# SCH_USB-Iker-Delicado_2025-02-14.net
KiCad netlist of a schematic drawn in EasyEDA
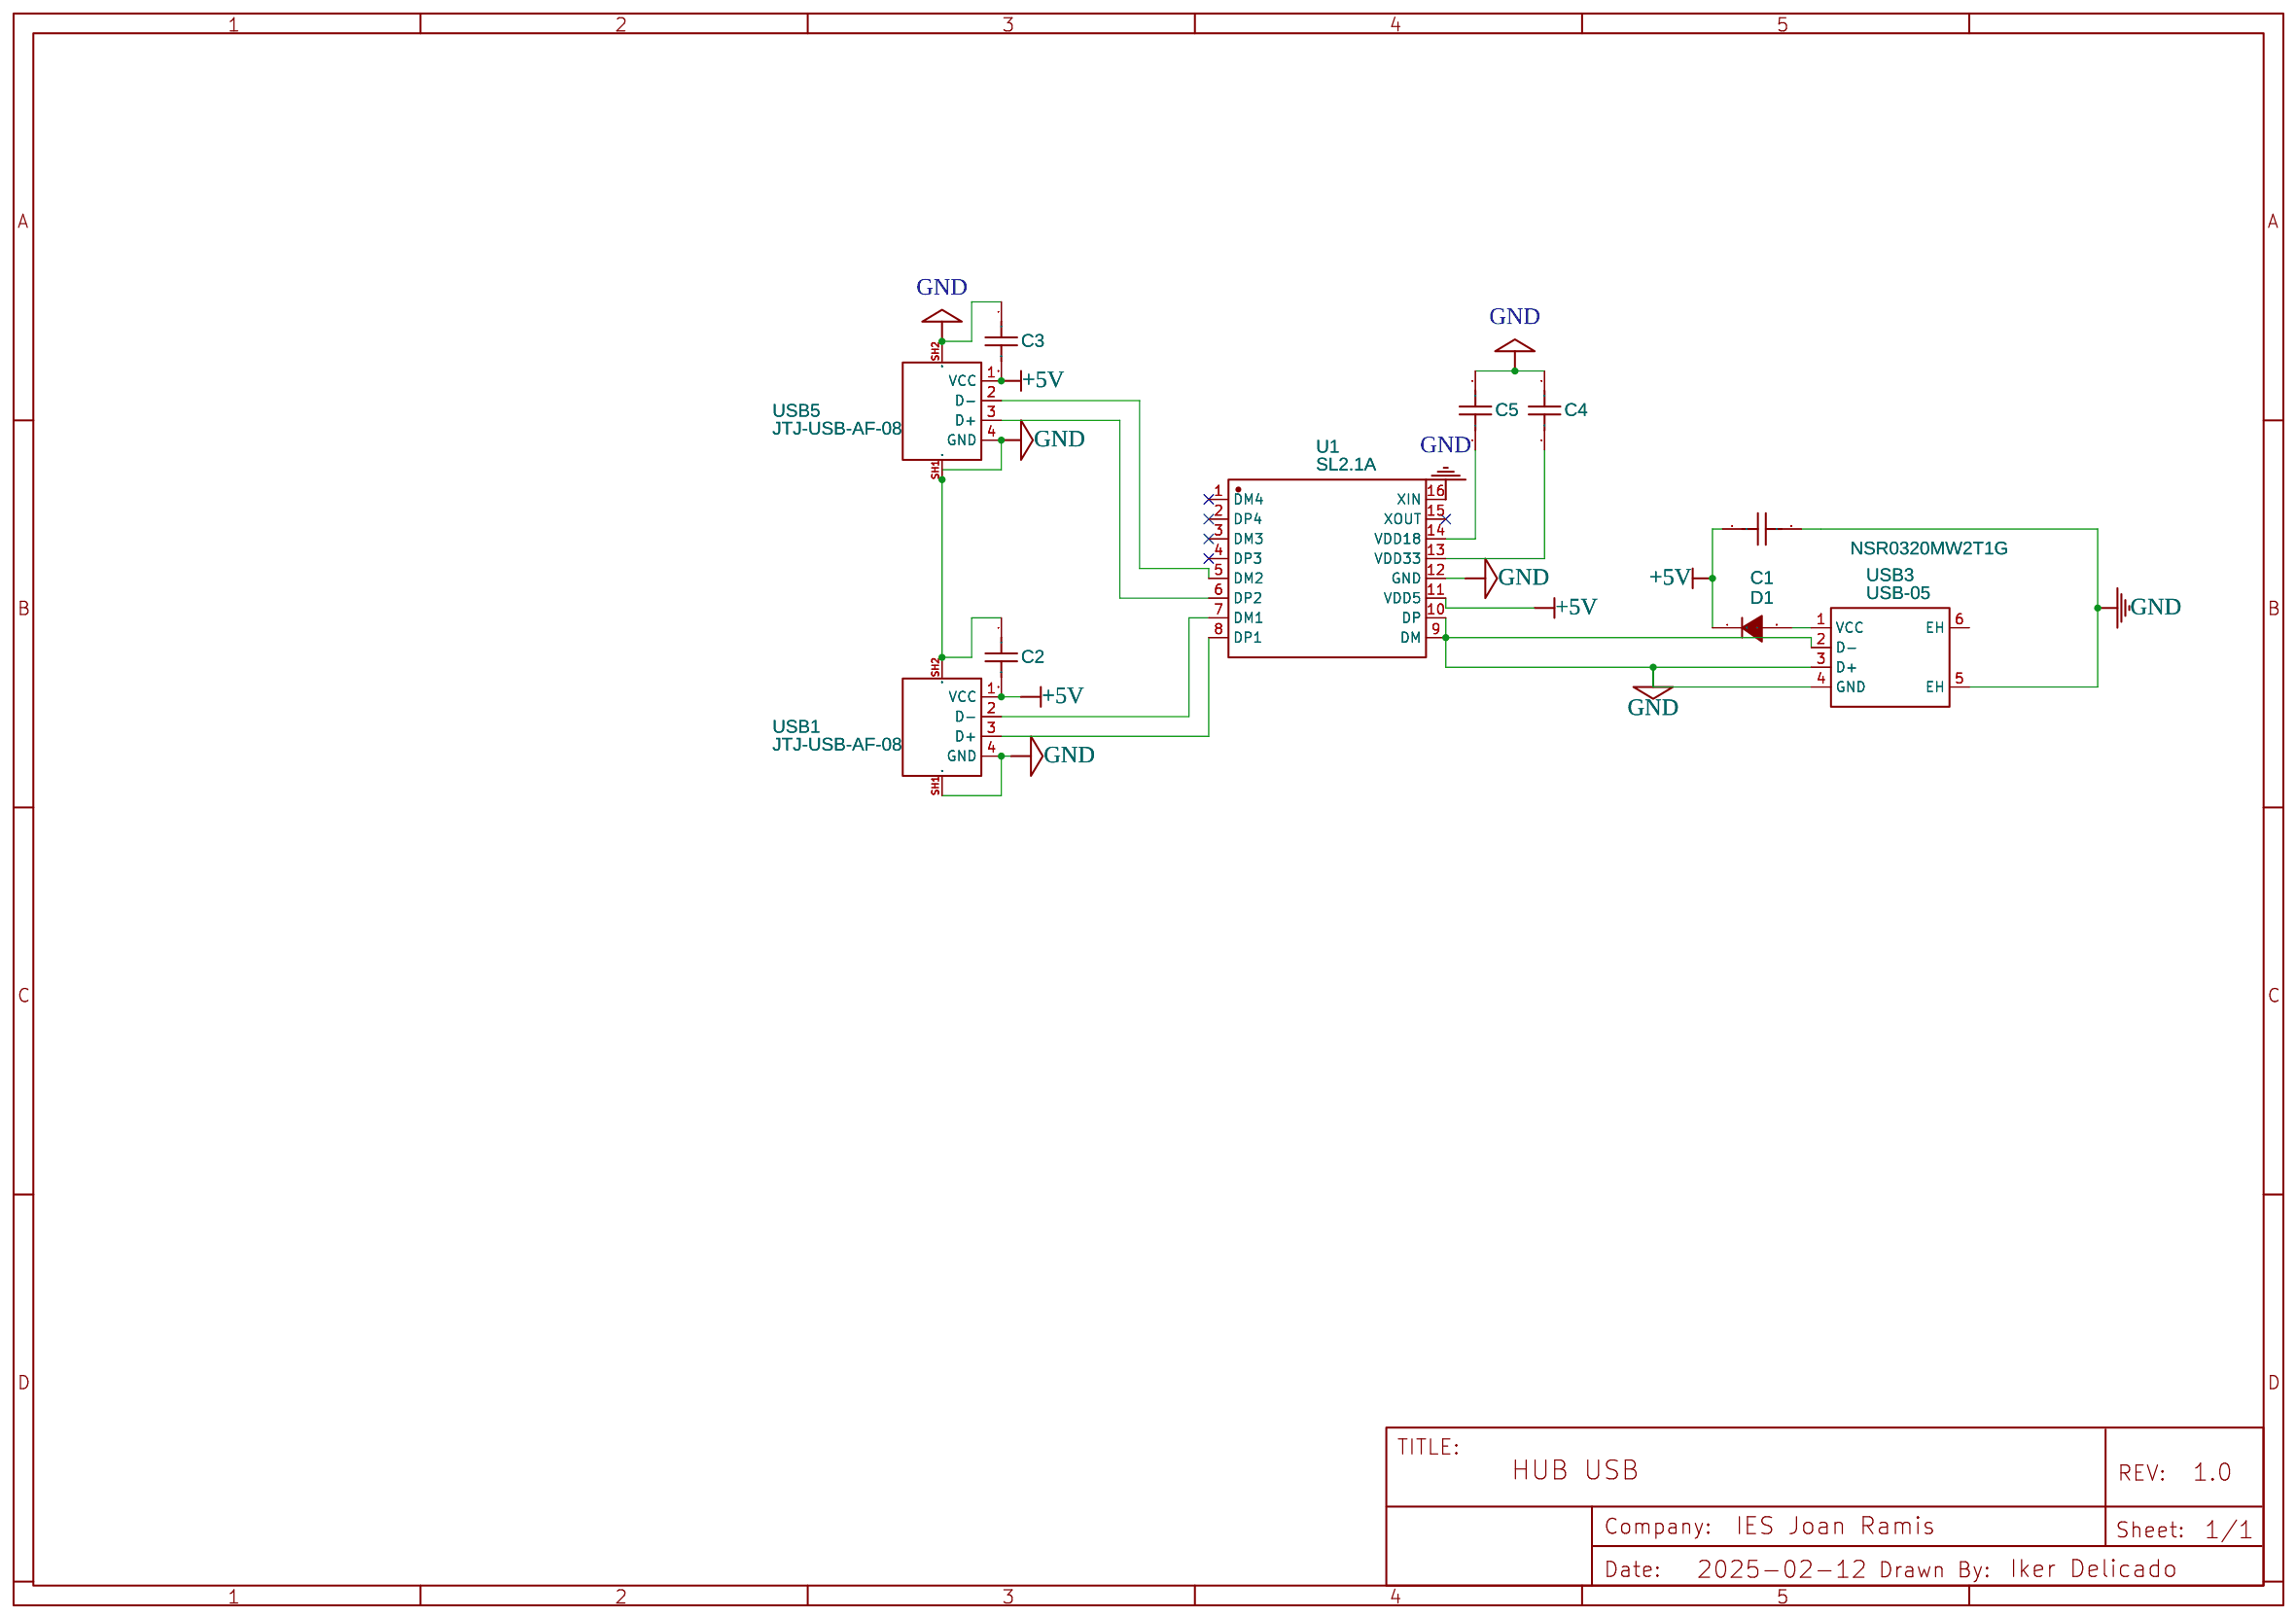
[diagram p0: schematic sheet]

(export (version "E")
  (design (tool "Eeschema 10.0.6"))
  (components
    (comp (ref "C1")
      (value "10uF")
      (fields
        (field (name "Manufacturer Part") "CL10A106KP8NNNC")
        (field (name "Manufacturer") "SAMSUNG(三星)")
      )
      (libsource (lib "") (part "CL10A106KP8NNNC"))
    )
    (comp (ref "C2")
      (value "10uF")
      (fields
        (field (name "Manufacturer Part") "CL10A106KP8NNNC")
        (field (name "Manufacturer") "SAMSUNG(三星)")
      )
      (libsource (lib "") (part "CL10A106KP8NNNC_1"))
    )
    (comp (ref "C3")
      (value "10uF")
      (fields
        (field (name "Manufacturer Part") "CL10A106KP8NNNC")
        (field (name "Manufacturer") "SAMSUNG(三星)")
      )
      (libsource (lib "") (part "CL10A106KP8NNNC_1"))
    )
    (comp (ref "C4")
      (value "10uF")
      (fields
        (field (name "Manufacturer Part") "CL10A106KP8NNNC")
        (field (name "Manufacturer") "SAMSUNG(三星)")
      )
      (libsource (lib "") (part "CL10A106KP8NNNC_1"))
    )
    (comp (ref "C5")
      (value "10uF")
      (fields
        (field (name "Manufacturer Part") "CL10A106KP8NNNC")
        (field (name "Manufacturer") "SAMSUNG(三星)")
      )
      (libsource (lib "") (part "CL10A106KP8NNNC_1"))
    )
    (comp (ref "D1")
      (value "NSR0320MW2T1G")
      (fields (field (name "Manufacturer") "onsemi(安森美)"))
      (libsource (lib "") (part "NSR0320MW2T1G"))
    )
    (comp (ref "U1")
      (value "SL2.1A")
      (fields (field (name "Manufacturer") "CoreChips(和芯润德)"))
      (libsource (lib "") (part "SL2.1A"))
    )
    (comp (ref "USB1")
      (value "JTJ-USB-AF-08")
      (fields (field (name "Manufacturer Part") "902-131A1011D10100") (field (name "Manufacturer") "精拓金"))
      (libsource (lib "") (part "JTJ-USB-AF-08"))
    )
    (comp (ref "USB3")
      (value "USB-05")
      (fields (field (name "Manufacturer") "SOFNG(硕方)"))
      (libsource (lib "") (part "USB-05"))
    )
    (comp (ref "USB5")
      (value "JTJ-USB-AF-08")
      (fields (field (name "Manufacturer Part") "902-131A1011D10100") (field (name "Manufacturer") "精拓金"))
      (libsource (lib "") (part "JTJ-USB-AF-08"))
    )
  )
  (nets
    (net (code "1") (name "+5V") (class "Default")
      (node (ref "C1") (pin "1") (pinfunction "1_1") (pintype "unspecified"))
      (node (ref "C2") (pin "2") (pinfunction "2_2") (pintype "unspecified"))
      (node (ref "C3") (pin "2") (pinfunction "2_2") (pintype "unspecified"))
      (node (ref "D1") (pin "1") (pinfunction "C_1") (pintype "unspecified"))
      (node (ref "U1") (pin "11") (pinfunction "VDD5_11") (pintype "unspecified"))
      (node (ref "USB1") (pin "1") (pinfunction "VCC_1") (pintype "input"))
      (node (ref "USB5") (pin "1") (pinfunction "VCC_1") (pintype "input"))
    )
    (net (code "2") (name "GND") (class "Default")
      (node (ref "C1") (pin "2") (pinfunction "2_2") (pintype "unspecified"))
      (node (ref "C2") (pin "1") (pinfunction "1_1") (pintype "unspecified"))
      (node (ref "C3") (pin "1") (pinfunction "1_1") (pintype "unspecified"))
      (node (ref "C4") (pin "1") (pinfunction "1_1") (pintype "unspecified"))
      (node (ref "C5") (pin "1") (pinfunction "1_1") (pintype "unspecified"))
      (node (ref "U1") (pin "10") (pinfunction "DP_10") (pintype "unspecified"))
      (node (ref "U1") (pin "12") (pinfunction "GND_12") (pintype "unspecified"))
      (node (ref "U1") (pin "16") (pinfunction "XIN_16") (pintype "unspecified"))
      (node (ref "U1") (pin "9") (pinfunction "DM_9") (pintype "unspecified"))
      (node (ref "USB1") (pin "4") (pinfunction "GND_4") (pintype "input"))
      (node (ref "USB1") (pin "SH1") (pinfunction "SH1_SH1") (pintype "unspecified"))
      (node (ref "USB1") (pin "SH2") (pinfunction "SH2_SH2") (pintype "unspecified"))
      (node (ref "USB3") (pin "2") (pinfunction "D-_2") (pintype "input"))
      (node (ref "USB3") (pin "3") (pinfunction "D+_3") (pintype "input"))
      (node (ref "USB3") (pin "4") (pinfunction "GND_4") (pintype "input"))
      (node (ref "USB3") (pin "5") (pinfunction "EH_5") (pintype "unspecified"))
      (node (ref "USB5") (pin "4") (pinfunction "GND_4") (pintype "input"))
      (node (ref "USB5") (pin "SH1") (pinfunction "SH1_SH1") (pintype "unspecified"))
      (node (ref "USB5") (pin "SH2") (pinfunction "SH2_SH2") (pintype "unspecified"))
    )
    (net (code "3") (name "Net-(D1-A)") (class "Default")
      (node (ref "D1") (pin "2") (pinfunction "A_2") (pintype "unspecified"))
      (node (ref "USB3") (pin "1") (pinfunction "VCC_1") (pintype "input"))
    )
    (net (code "4") (name "Net-(U1-DM1)") (class "Default")
      (node (ref "U1") (pin "7") (pinfunction "DM1_7") (pintype "unspecified"))
      (node (ref "USB1") (pin "2") (pinfunction "D-_2") (pintype "input"))
    )
    (net (code "5") (name "Net-(U1-DM2)") (class "Default")
      (node (ref "U1") (pin "5") (pinfunction "DM2_5") (pintype "unspecified"))
      (node (ref "USB5") (pin "2") (pinfunction "D-_2") (pintype "input"))
    )
    (net (code "6") (name "Net-(U1-DP1)") (class "Default")
      (node (ref "U1") (pin "8") (pinfunction "DP1_8") (pintype "unspecified"))
      (node (ref "USB1") (pin "3") (pinfunction "D+_3") (pintype "input"))
    )
    (net (code "7") (name "Net-(U1-DP2)") (class "Default")
      (node (ref "U1") (pin "6") (pinfunction "DP2_6") (pintype "unspecified"))
      (node (ref "USB5") (pin "3") (pinfunction "D+_3") (pintype "input"))
    )
    (net (code "8") (name "Net-(U1-VDD18)") (class "Default")
      (node (ref "C5") (pin "2") (pinfunction "2_2") (pintype "unspecified"))
      (node (ref "U1") (pin "14") (pinfunction "VDD18_14") (pintype "unspecified"))
    )
    (net (code "9") (name "Net-(U1-VDD33)") (class "Default")
      (node (ref "C4") (pin "2") (pinfunction "2_2") (pintype "unspecified"))
      (node (ref "U1") (pin "13") (pinfunction "VDD33_13") (pintype "unspecified"))
    )
    (net (code "10") (name "unconnected-(U1-DM3-Pad3)") (class "Default")
      (node (ref "U1") (pin "3") (pinfunction "DM3_3") (pintype "unspecified+no_connect"))
    )
    (net (code "11") (name "unconnected-(U1-DM4-Pad1)") (class "Default")
      (node (ref "U1") (pin "1") (pinfunction "DM4_1") (pintype "unspecified+no_connect"))
    )
    (net (code "12") (name "unconnected-(U1-DP3-Pad4)") (class "Default")
      (node (ref "U1") (pin "4") (pinfunction "DP3_4") (pintype "unspecified+no_connect"))
    )
    (net (code "13") (name "unconnected-(U1-DP4-Pad2)") (class "Default")
      (node (ref "U1") (pin "2") (pinfunction "DP4_2") (pintype "unspecified+no_connect"))
    )
    (net (code "14") (name "unconnected-(U1-XOUT-Pad15)") (class "Default")
      (node (ref "U1") (pin "15") (pinfunction "XOUT_15") (pintype "unspecified+no_connect"))
    )
    (net (code "15") (name "unconnected-(USB3-EH-Pad6)") (class "Default")
      (node (ref "USB3") (pin "6") (pinfunction "EH_6") (pintype "unspecified"))
    )
  )
)
